# 1_MCU.net
KiCad netlist of a schematic drawn in Altium Designer
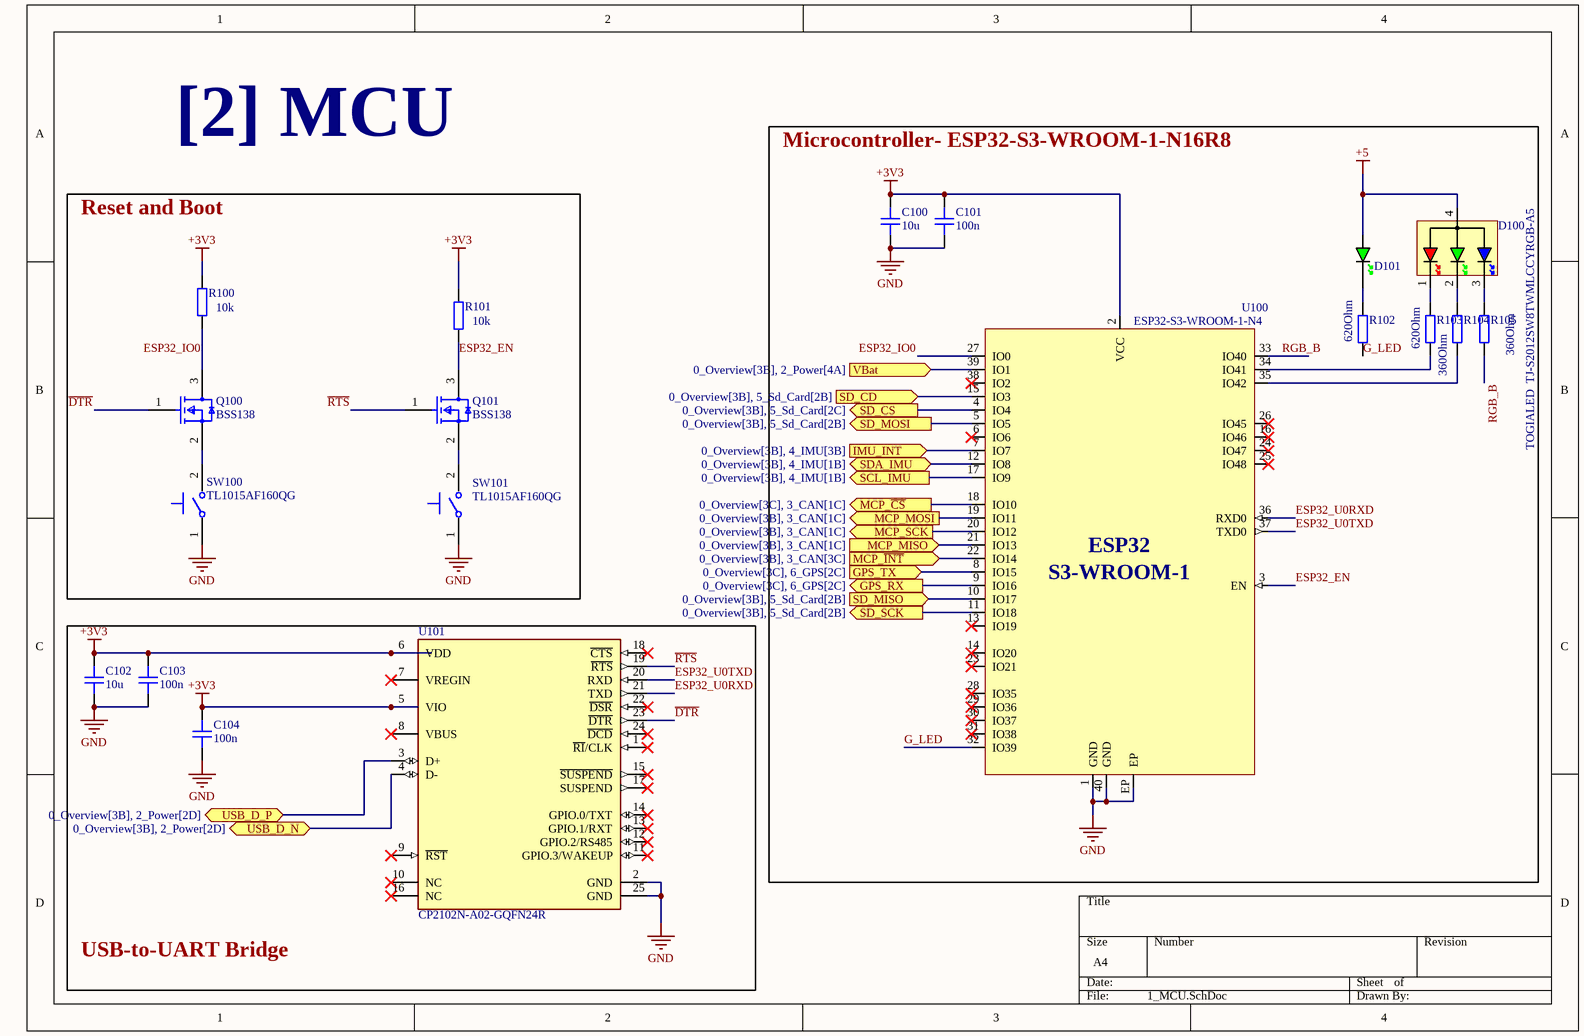
[diagram p0: 1_MCU.SchDoc]

(export (version "E")
  (design (tool "Eeschema 10.0.6"))
  (components
    (comp (ref "C100")
      (value "10u")
      (footprint "CAP_0805")
      (description "Capacitor SMD 0805")
      (libsource (lib "Schematic-Lib-PhilsLab") (part "CAP_0805"))
    )
    (comp (ref "C101")
      (value "100n")
      (footprint "CAP_0603")
      (description "Capacitor SMD 0603")
      (libsource (lib "Schematic-Lib-PhilsLab") (part "CAP_0603"))
    )
    (comp (ref "C102")
      (value "10u")
      (footprint "CAP_0805")
      (description "Capacitor SMD 0805")
      (libsource (lib "Schematic-Lib-PhilsLab") (part "CAP_0805"))
    )
    (comp (ref "C103")
      (value "100n")
      (footprint "CAP_0603")
      (description "Capacitor SMD 0603")
      (libsource (lib "Schematic-Lib-PhilsLab") (part "CAP_0603"))
    )
    (comp (ref "C104")
      (value "100n")
      (footprint "CAP_0603")
      (description "Capacitor SMD 0603")
      (libsource (lib "Schematic-Lib-PhilsLab") (part "CAP_0603"))
    )
    (comp (ref "D100")
      (value "TOGIALED  TJ-S2012SW8TWMLCCYRGB-A5")
      (footprint "150080M153000")
      (description "RGB LED Common Anode SMD Diffused 0805 Top View")
      (fields (field (name "MANUFACTURER") "Wurth") (field (name "MANUFACTURER PART NUMBER") "150080M153000"))
      (libsource (lib "Schematic-Lib-PhilsLab") (part "150080M153000"))
    )
    (comp (ref "D101")
      (value "GREEN")
      (footprint "LED_0603_GREEN")
      (description "LED 0603 GREEN SMD")
      (libsource (lib "Schematic-Lib-PhilsLab") (part "LED_0603_GREEN"))
    )
    (comp (ref "Q100")
      (value "BSS138")
      (footprint "FP-318-08-IPC_B")
      (description "MOSFET N-CH 50V 220MA SOT-23")
      (libsource (lib "Altium Content Vault") (part "3b9c635fedb024a5347a57b145af9cc"))
    )
    (comp (ref "Q101")
      (value "BSS138")
      (footprint "FP-318-08-IPC_B")
      (description "MOSFET N-CH 50V 220MA SOT-23")
      (libsource (lib "Altium Content Vault") (part "3b9c635fedb024a5347a57b145af9cc"))
    )
    (comp (ref "R100")
      (value "10k")
      (footprint "RES_0603")
      (description "Resistor SMD 0603")
      (libsource (lib "Schematic-Lib-PhilsLab") (part "RES_0603"))
    )
    (comp (ref "R101")
      (value "10k")
      (footprint "RES_0603")
      (description "Resistor SMD 0603")
      (libsource (lib "Schematic-Lib-PhilsLab") (part "RES_0603"))
    )
    (comp (ref "R102")
      (value "620Ohm")
      (footprint "RES_0603")
      (description "Resistor SMD 0603")
      (libsource (lib "Schematic-Lib-PhilsLab") (part "RES_0603"))
    )
    (comp (ref "R103")
      (value "620Ohm")
      (footprint "RES_0603")
      (description "Resistor SMD 0603")
      (libsource (lib "Schematic-Lib-PhilsLab") (part "RES_0603"))
    )
    (comp (ref "R104")
      (value "360Ohm")
      (footprint "RES_0603")
      (description "Resistor SMD 0603")
      (libsource (lib "Schematic-Lib-PhilsLab") (part "RES_0603"))
    )
    (comp (ref "R105")
      (value "360Ohm")
      (footprint "RES_0603")
      (description "Resistor SMD 0603")
      (libsource (lib "Schematic-Lib-PhilsLab") (part "RES_0603"))
    )
    (comp (ref "SW100")
      (value "TL1015AF160QG")
      (footprint "FP-TL1015AF160QG-MFG")
      (description "SWITCH TACTILE SPST-NO 0.05A 12V")
      (libsource (lib "Altium Content Vault") (part "2041f8efb62e6aaa548c9fd35e2c2f1"))
    )
    (comp (ref "SW101")
      (value "TL1015AF160QG")
      (footprint "FP-TL1015AF160QG-MFG")
      (description "SWITCH TACTILE SPST-NO 0.05A 12V")
      (libsource (lib "Altium Content Vault") (part "2041f8efb62e6aaa548c9fd35e2c2f1"))
    )
    (comp (ref "U100")
      (value "ESP32-S3-WROOM-1-N4")
      (footprint "ESP32-S3-WROOM-1")
      (fields (field (name "MANUFACTURER") "Espressif"))
      (libsource (lib "Schematic-Lib-PhilsLab") (part "ESP32-S3-WROOM-1-N4"))
    )
    (comp (ref "U101")
      (value "CP2102N-A02-GQFN24R")
      (footprint "FP-CP2102N-A02-GQFN24R-MFG")
      (description "IC USB TO UART BRIDGE QFN24")
      (libsource (lib "Altium Content Vault") (part "83e8975dde71cc570f99d23b4d888c9"))
    )
  )
  (nets
    (net (code "1") (name "+3V3") (class "Default")
      (node (ref "C100") (pin "2") (pinfunction "2_2") (pintype "passive"))
      (node (ref "C101") (pin "1") (pinfunction "1_1") (pintype "passive"))
      (node (ref "C102") (pin "2") (pinfunction "2_2") (pintype "passive"))
      (node (ref "C103") (pin "1") (pinfunction "1_1") (pintype "passive"))
      (node (ref "C104") (pin "1") (pinfunction "1_1") (pintype "passive"))
      (node (ref "R100") (pin "2") (pinfunction "2_2") (pintype "passive"))
      (node (ref "R101") (pin "2") (pinfunction "2_2") (pintype "passive"))
      (node (ref "U100") (pin "2") (pinfunction "VCC_2") (pintype "power_in"))
      (node (ref "U101") (pin "5") (pinfunction "VIO_5") (pintype "power_in"))
      (node (ref "U101") (pin "6") (pinfunction "VDD_6") (pintype "power_in"))
    )
    (net (code "2") (name "+5") (class "Default")
      (node (ref "D100") (pin "4") (pinfunction "AC_4") (pintype "passive"))
      (node (ref "D101") (pin "A") (pinfunction "A_A") (pintype "passive"))
    )
    (net (code "3") (name "/ESP32_EN") (class "Default")
      (node (ref "Q101") (pin "3") (pinfunction "D_3") (pintype "passive"))
      (node (ref "R101") (pin "1") (pinfunction "1_1") (pintype "passive"))
      (node (ref "U100") (pin "3") (pinfunction "EN_3") (pintype "input"))
    )
    (net (code "4") (name "/ESP32_IO0") (class "Default")
      (node (ref "Q100") (pin "3") (pinfunction "D_3") (pintype "passive"))
      (node (ref "R100") (pin "1") (pinfunction "1_1") (pintype "passive"))
      (node (ref "U100") (pin "27") (pinfunction "IO0_27") (pintype "bidirectional"))
    )
    (net (code "5") (name "/ESP32_U0RXD") (class "Default")
      (node (ref "U100") (pin "36") (pinfunction "RXD0_36") (pintype "input"))
      (node (ref "U101") (pin "21") (pinfunction "TXD_21") (pintype "output"))
    )
    (net (code "6") (name "/ESP32_U0TXD") (class "Default")
      (node (ref "U100") (pin "37") (pinfunction "TXD0_37") (pintype "output"))
      (node (ref "U101") (pin "20") (pinfunction "RXD_20") (pintype "input"))
    )
    (net (code "7") (name "/GPS_RX") (class "Default")
      (node (ref "U100") (pin "9") (pinfunction "IO16_9") (pintype "bidirectional"))
    )
    (net (code "8") (name "/GPS_TX") (class "Default")
      (node (ref "U100") (pin "8") (pinfunction "IO15_8") (pintype "bidirectional"))
    )
    (net (code "9") (name "/G_LED") (class "Default")
      (node (ref "R102") (pin "1") (pinfunction "1_1") (pintype "passive"))
      (node (ref "U100") (pin "32") (pinfunction "IO39_32") (pintype "bidirectional"))
    )
    (net (code "10") (name "/IMU_INT") (class "Default")
      (node (ref "U100") (pin "7") (pinfunction "IO7_7") (pintype "bidirectional"))
    )
    (net (code "11") (name "/MCP_MISO") (class "Default")
      (node (ref "U100") (pin "21") (pinfunction "IO13_21") (pintype "bidirectional"))
    )
    (net (code "12") (name "/MCP_MOSI") (class "Default")
      (node (ref "U100") (pin "19") (pinfunction "IO11_19") (pintype "bidirectional"))
    )
    (net (code "13") (name "/MCP_SCK") (class "Default")
      (node (ref "U100") (pin "20") (pinfunction "IO12_20") (pintype "bidirectional"))
    )
    (net (code "14") (name "/MCP_~{CS}") (class "Default")
      (node (ref "U100") (pin "18") (pinfunction "IO10_18") (pintype "bidirectional"))
    )
    (net (code "15") (name "/MCP_~{INT}") (class "Default")
      (node (ref "U100") (pin "22") (pinfunction "IO14_22") (pintype "bidirectional"))
    )
    (net (code "16") (name "/RGB_B") (class "Default")
      (node (ref "R105") (pin "1") (pinfunction "1_1") (pintype "passive"))
      (node (ref "U100") (pin "33") (pinfunction "IO40_33") (pintype "bidirectional"))
    )
    (net (code "17") (name "/SCL_IMU") (class "Default")
      (node (ref "U100") (pin "17") (pinfunction "IO9_17") (pintype "bidirectional"))
    )
    (net (code "18") (name "/SDA_IMU") (class "Default")
      (node (ref "U100") (pin "12") (pinfunction "IO8_12") (pintype "bidirectional"))
    )
    (net (code "19") (name "/SD_CD") (class "Default")
      (node (ref "U100") (pin "15") (pinfunction "IO3_15") (pintype "bidirectional"))
    )
    (net (code "20") (name "/SD_CS") (class "Default")
      (node (ref "U100") (pin "4") (pinfunction "IO4_4") (pintype "bidirectional"))
    )
    (net (code "21") (name "/SD_MISO") (class "Default")
      (node (ref "U100") (pin "10") (pinfunction "IO17_10") (pintype "bidirectional"))
    )
    (net (code "22") (name "/SD_MOSI") (class "Default")
      (node (ref "U100") (pin "5") (pinfunction "IO5_5") (pintype "bidirectional"))
    )
    (net (code "23") (name "/SD_SCK") (class "Default")
      (node (ref "U100") (pin "11") (pinfunction "IO18_11") (pintype "bidirectional"))
    )
    (net (code "24") (name "/USB_D_N") (class "Default")
      (node (ref "U101") (pin "4") (pinfunction "D-_4") (pintype "bidirectional"))
    )
    (net (code "25") (name "/USB_D_P") (class "Default")
      (node (ref "U101") (pin "3") (pinfunction "D+_3") (pintype "bidirectional"))
    )
    (net (code "26") (name "/VBat") (class "Default")
      (node (ref "U100") (pin "39") (pinfunction "IO1_39") (pintype "bidirectional"))
    )
    (net (code "27") (name "/~{DTR}") (class "Default")
      (node (ref "Q100") (pin "1") (pinfunction "G_1") (pintype "passive"))
      (node (ref "U101") (pin "23") (pinfunction "~{DTR}_23") (pintype "output"))
    )
    (net (code "28") (name "/~{RTS}") (class "Default")
      (node (ref "Q101") (pin "1") (pinfunction "G_1") (pintype "passive"))
      (node (ref "U101") (pin "19") (pinfunction "~{RTS}_19") (pintype "output"))
    )
    (net (code "29") (name "GND") (class "Default")
      (node (ref "C100") (pin "1") (pinfunction "1_1") (pintype "passive"))
      (node (ref "C101") (pin "2") (pinfunction "2_2") (pintype "passive"))
      (node (ref "C102") (pin "1") (pinfunction "1_1") (pintype "passive"))
      (node (ref "C103") (pin "2") (pinfunction "2_2") (pintype "passive"))
      (node (ref "C104") (pin "2") (pinfunction "2_2") (pintype "passive"))
      (node (ref "SW100") (pin "1") (pinfunction "1_1") (pintype "passive"))
      (node (ref "SW101") (pin "1") (pinfunction "1_1") (pintype "passive"))
      (node (ref "U100") (pin "1") (pinfunction "GND_1") (pintype "power_in"))
      (node (ref "U100") (pin "40") (pinfunction "GND_40") (pintype "power_in"))
      (node (ref "U100") (pin "EP") (pinfunction "EP_EP") (pintype "power_in"))
      (node (ref "U101") (pin "2") (pinfunction "GND_2") (pintype "power_in"))
      (node (ref "U101") (pin "25") (pinfunction "GND_25") (pintype "power_in"))
    )
    (net (code "30") (name "Net-(D100-CB)") (class "Default")
      (node (ref "D100") (pin "3") (pinfunction "CB_3") (pintype "passive"))
      (node (ref "R105") (pin "2") (pinfunction "2_2") (pintype "passive"))
    )
    (net (code "31") (name "Net-(D100-CG)") (class "Default")
      (node (ref "D100") (pin "2") (pinfunction "CG_2") (pintype "passive"))
      (node (ref "R104") (pin "2") (pinfunction "2_2") (pintype "passive"))
    )
    (net (code "32") (name "Net-(D100-CR)") (class "Default")
      (node (ref "D100") (pin "1") (pinfunction "CR_1") (pintype "passive"))
      (node (ref "R103") (pin "2") (pinfunction "2_2") (pintype "passive"))
    )
    (net (code "33") (name "Net-(D101-PadK)") (class "Default")
      (node (ref "D101") (pin "K") (pinfunction "K_K") (pintype "passive"))
      (node (ref "R102") (pin "2") (pinfunction "2_2") (pintype "passive"))
    )
    (net (code "34") (name "Net-(Q100-S)") (class "Default")
      (node (ref "Q100") (pin "2") (pinfunction "S_2") (pintype "passive"))
      (node (ref "SW100") (pin "2") (pinfunction "2_2") (pintype "passive"))
    )
    (net (code "35") (name "Net-(Q101-S)") (class "Default")
      (node (ref "Q101") (pin "2") (pinfunction "S_2") (pintype "passive"))
      (node (ref "SW101") (pin "2") (pinfunction "2_2") (pintype "passive"))
    )
    (net (code "36") (name "Net-(U100-IO41)") (class "Default")
      (node (ref "R103") (pin "1") (pinfunction "1_1") (pintype "passive"))
      (node (ref "U100") (pin "34") (pinfunction "IO41_34") (pintype "bidirectional"))
    )
    (net (code "37") (name "Net-(U100-IO42)") (class "Default")
      (node (ref "R104") (pin "1") (pinfunction "1_1") (pintype "passive"))
      (node (ref "U100") (pin "35") (pinfunction "IO42_35") (pintype "bidirectional"))
    )
    (net (code "38") (name "unconnected-(U100-IO2-Pad38)") (class "Default")
      (node (ref "U100") (pin "38") (pinfunction "IO2_38") (pintype "bidirectional+no_connect"))
    )
    (net (code "39") (name "unconnected-(U100-IO6-Pad6)") (class "Default")
      (node (ref "U100") (pin "6") (pinfunction "IO6_6") (pintype "bidirectional+no_connect"))
    )
    (net (code "40") (name "unconnected-(U100-IO19-Pad13)") (class "Default")
      (node (ref "U100") (pin "13") (pinfunction "IO19_13") (pintype "bidirectional+no_connect"))
    )
    (net (code "41") (name "unconnected-(U100-IO20-Pad14)") (class "Default")
      (node (ref "U100") (pin "14") (pinfunction "IO20_14") (pintype "bidirectional+no_connect"))
    )
    (net (code "42") (name "unconnected-(U100-IO21-Pad23)") (class "Default")
      (node (ref "U100") (pin "23") (pinfunction "IO21_23") (pintype "bidirectional+no_connect"))
    )
    (net (code "43") (name "unconnected-(U100-IO35-Pad28)") (class "Default")
      (node (ref "U100") (pin "28") (pinfunction "IO35_28") (pintype "bidirectional+no_connect"))
    )
    (net (code "44") (name "unconnected-(U100-IO36-Pad29)") (class "Default")
      (node (ref "U100") (pin "29") (pinfunction "IO36_29") (pintype "bidirectional+no_connect"))
    )
    (net (code "45") (name "unconnected-(U100-IO37-Pad30)") (class "Default")
      (node (ref "U100") (pin "30") (pinfunction "IO37_30") (pintype "bidirectional+no_connect"))
    )
    (net (code "46") (name "unconnected-(U100-IO38-Pad31)") (class "Default")
      (node (ref "U100") (pin "31") (pinfunction "IO38_31") (pintype "bidirectional+no_connect"))
    )
    (net (code "47") (name "unconnected-(U100-IO45-Pad26)") (class "Default")
      (node (ref "U100") (pin "26") (pinfunction "IO45_26") (pintype "bidirectional+no_connect"))
    )
    (net (code "48") (name "unconnected-(U100-IO46-Pad16)") (class "Default")
      (node (ref "U100") (pin "16") (pinfunction "IO46_16") (pintype "bidirectional+no_connect"))
    )
    (net (code "49") (name "unconnected-(U100-IO47-Pad24)") (class "Default")
      (node (ref "U100") (pin "24") (pinfunction "IO47_24") (pintype "bidirectional+no_connect"))
    )
    (net (code "50") (name "unconnected-(U100-IO48-Pad25)") (class "Default")
      (node (ref "U100") (pin "25") (pinfunction "IO48_25") (pintype "bidirectional+no_connect"))
    )
    (net (code "51") (name "unconnected-(U101-GPIO.0{slash}TXT-Pad14)") (class "Default")
      (node (ref "U101") (pin "14") (pinfunction "GPIO.0/TXT_14") (pintype "bidirectional+no_connect"))
    )
    (net (code "52") (name "unconnected-(U101-GPIO.1{slash}RXT-Pad13)") (class "Default")
      (node (ref "U101") (pin "13") (pinfunction "GPIO.1/RXT_13") (pintype "bidirectional+no_connect"))
    )
    (net (code "53") (name "unconnected-(U101-GPIO.2{slash}RS485-Pad12)") (class "Default")
      (node (ref "U101") (pin "12") (pinfunction "GPIO.2/RS485_12") (pintype "bidirectional+no_connect"))
    )
    (net (code "54") (name "unconnected-(U101-GPIO.3{slash}WAKEUP-Pad11)") (class "Default")
      (node (ref "U101") (pin "11") (pinfunction "GPIO.3/WAKEUP_11") (pintype "bidirectional+no_connect"))
    )
    (net (code "55") (name "unconnected-(U101-NC-Pad10)") (class "Default")
      (node (ref "U101") (pin "10") (pinfunction "NC_10") (pintype "passive+no_connect"))
    )
    (net (code "56") (name "unconnected-(U101-NC-Pad16)") (class "Default")
      (node (ref "U101") (pin "16") (pinfunction "NC_16") (pintype "passive+no_connect"))
    )
    (net (code "57") (name "unconnected-(U101-SUSPEND-Pad17)") (class "Default")
      (node (ref "U101") (pin "17") (pinfunction "SUSPEND_17") (pintype "output+no_connect"))
    )
    (net (code "58") (name "unconnected-(U101-VBUS-Pad8)") (class "Default")
      (node (ref "U101") (pin "8") (pinfunction "VBUS_8") (pintype "power_in+no_connect"))
    )
    (net (code "59") (name "unconnected-(U101-VREGIN-Pad7)") (class "Default")
      (node (ref "U101") (pin "7") (pinfunction "VREGIN_7") (pintype "power_in+no_connect"))
    )
    (net (code "60") (name "unconnected-(U101-~{CTS}-Pad18)") (class "Default")
      (node (ref "U101") (pin "18") (pinfunction "~{CTS}_18") (pintype "input+no_connect"))
    )
    (net (code "61") (name "unconnected-(U101-~{DCD}-Pad24)") (class "Default")
      (node (ref "U101") (pin "24") (pinfunction "~{DCD}_24") (pintype "input+no_connect"))
    )
    (net (code "62") (name "unconnected-(U101-~{DSR}-Pad22)") (class "Default")
      (node (ref "U101") (pin "22") (pinfunction "~{DSR}_22") (pintype "input+no_connect"))
    )
    (net (code "63") (name "unconnected-(U101-~{RI}{slash}CLK-Pad1)") (class "Default")
      (node (ref "U101") (pin "1") (pinfunction "~{RI}/CLK_1") (pintype "input+no_connect"))
    )
    (net (code "64") (name "unconnected-(U101-~{RST}-Pad9)") (class "Default")
      (node (ref "U101") (pin "9") (pinfunction "~{RST}_9") (pintype "input+no_connect"))
    )
    (net (code "65") (name "unconnected-(U101-~{SUSPEND}-Pad15)") (class "Default")
      (node (ref "U101") (pin "15") (pinfunction "~{SUSPEND}_15") (pintype "output+no_connect"))
    )
  )
)
